# Audio-Beamformer_FPGA_V1_0.net
KiCad netlist of a schematic drawn in Altium Designer
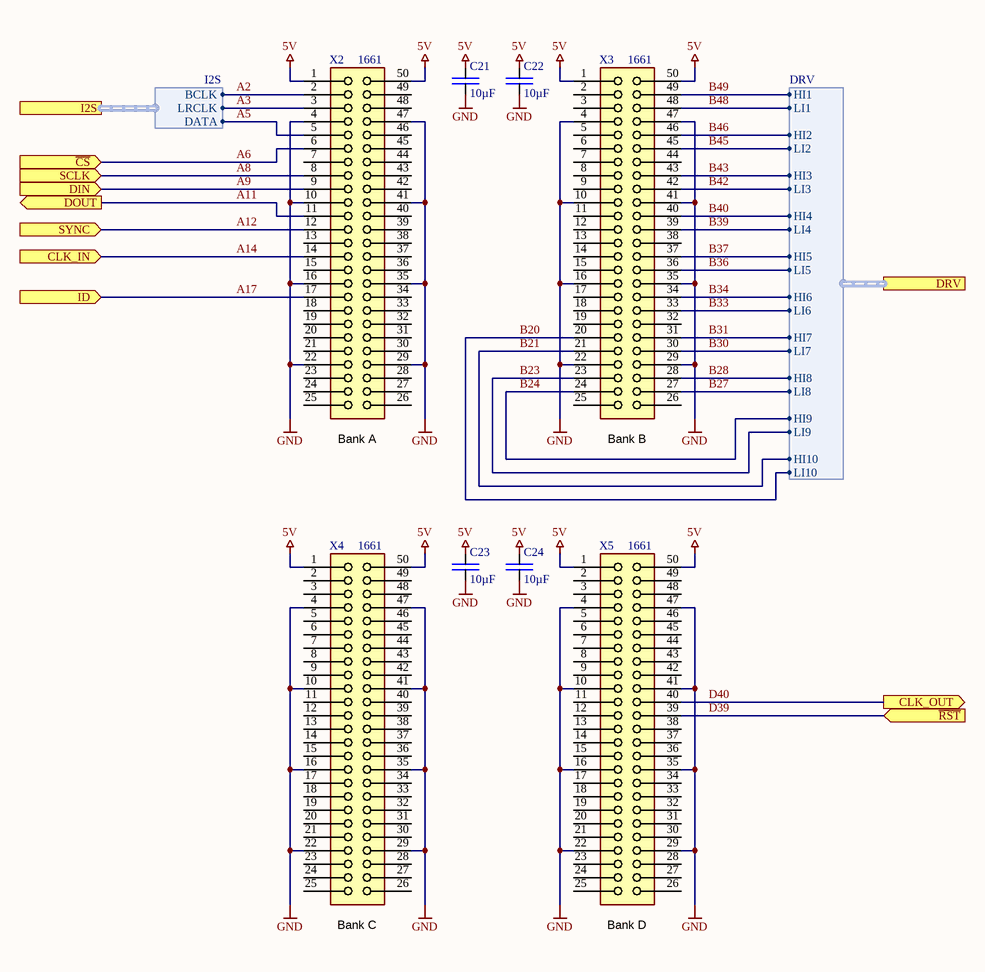
[diagram p0: Audio-Beamformer_FPGA_V1.0.SchDoc]

(export (version "E")
  (design (tool "Eeschema 10.0.6"))
  (components
    (comp (ref "C21")
      (value "10µF")
      (footprint "SMD Keramikkondensator 1206")
      (description "CAP-MK")
      (libsource (lib "AudioAmp") (part "C-CAPACITOR"))
    )
    (comp (ref "C22")
      (value "10µF")
      (footprint "SMD Keramikkondensator 1206")
      (description "CAP-MK")
      (libsource (lib "AudioAmp") (part "C-CAPACITOR"))
    )
    (comp (ref "C23")
      (value "10µF")
      (footprint "SMD Keramikkondensator 1206")
      (description "CAP-MK")
      (libsource (lib "AudioAmp") (part "C-CAPACITOR"))
    )
    (comp (ref "C24")
      (value "10µF")
      (footprint "SMD Keramikkondensator 1206")
      (description "CAP-MK")
      (libsource (lib "AudioAmp") (part "C-CAPACITOR"))
    )
    (comp (ref "X2")
      (value "1661")
      (footprint "SMD Connector (1661)")
      (description "Board-to-Board Connector (Receptacle)")
      (libsource (lib "Quad-Stage-Prototype") (part "X-4UCON_1661"))
    )
    (comp (ref "X3")
      (value "1661")
      (footprint "SMD Connector (1661)")
      (description "Board-to-Board Connector (Receptacle)")
      (libsource (lib "Quad-Stage-Prototype") (part "X-4UCON_1661"))
    )
    (comp (ref "X4")
      (value "1661")
      (footprint "SMD Connector (1661)")
      (description "Board-to-Board Connector (Receptacle)")
      (libsource (lib "Quad-Stage-Prototype") (part "X-4UCON_1661"))
    )
    (comp (ref "X5")
      (value "1661")
      (footprint "SMD Connector (1661)")
      (description "Board-to-Board Connector (Receptacle)")
      (libsource (lib "Quad-Stage-Prototype") (part "X-4UCON_1661"))
    )
  )
  (nets
    (net (code "3") (name "/A2") (class "Default")
      (node (ref "X2") (pin "2") (pinfunction "2_2") (pintype "passive"))
    )
    (net (code "4") (name "/A3") (class "Default")
      (node (ref "X2") (pin "3") (pinfunction "3_3") (pintype "passive"))
    )
    (net (code "5") (name "/A5") (class "Default")
      (node (ref "X2") (pin "5") (pinfunction "5_5") (pintype "passive"))
    )
    (net (code "6") (name "/A6") (class "Default")
      (node (ref "X2") (pin "6") (pinfunction "6_6") (pintype "passive"))
    )
    (net (code "7") (name "/A8") (class "Default")
      (node (ref "X2") (pin "8") (pinfunction "8_8") (pintype "passive"))
    )
    (net (code "8") (name "/A9") (class "Default")
      (node (ref "X2") (pin "9") (pinfunction "9_9") (pintype "passive"))
    )
    (net (code "9") (name "/A11") (class "Default")
      (node (ref "X2") (pin "11") (pinfunction "11_11") (pintype "passive"))
    )
    (net (code "10") (name "/A12") (class "Default")
      (node (ref "X2") (pin "12") (pinfunction "12_12") (pintype "passive"))
    )
    (net (code "11") (name "/A14") (class "Default")
      (node (ref "X2") (pin "14") (pinfunction "14_14") (pintype "passive"))
    )
    (net (code "12") (name "/A17") (class "Default")
      (node (ref "X2") (pin "17") (pinfunction "17_17") (pintype "passive"))
    )
    (net (code "13") (name "/B20") (class "Default")
      (node (ref "X3") (pin "20") (pinfunction "20_20") (pintype "passive"))
    )
    (net (code "14") (name "/B21") (class "Default")
      (node (ref "X3") (pin "21") (pinfunction "21_21") (pintype "passive"))
    )
    (net (code "15") (name "/B23") (class "Default")
      (node (ref "X3") (pin "23") (pinfunction "23_23") (pintype "passive"))
    )
    (net (code "16") (name "/B24") (class "Default")
      (node (ref "X3") (pin "24") (pinfunction "24_24") (pintype "passive"))
    )
    (net (code "17") (name "/B27") (class "Default")
      (node (ref "X3") (pin "27") (pinfunction "27_27") (pintype "passive"))
    )
    (net (code "18") (name "/B28") (class "Default")
      (node (ref "X3") (pin "28") (pinfunction "28_28") (pintype "passive"))
    )
    (net (code "19") (name "/B30") (class "Default")
      (node (ref "X3") (pin "30") (pinfunction "30_30") (pintype "passive"))
    )
    (net (code "20") (name "/B31") (class "Default")
      (node (ref "X3") (pin "31") (pinfunction "31_31") (pintype "passive"))
    )
    (net (code "21") (name "/B33") (class "Default")
      (node (ref "X3") (pin "33") (pinfunction "33_33") (pintype "passive"))
    )
    (net (code "22") (name "/B34") (class "Default")
      (node (ref "X3") (pin "34") (pinfunction "34_34") (pintype "passive"))
    )
    (net (code "23") (name "/B36") (class "Default")
      (node (ref "X3") (pin "36") (pinfunction "36_36") (pintype "passive"))
    )
    (net (code "24") (name "/B37") (class "Default")
      (node (ref "X3") (pin "37") (pinfunction "37_37") (pintype "passive"))
    )
    (net (code "25") (name "/B39") (class "Default")
      (node (ref "X3") (pin "39") (pinfunction "39_39") (pintype "passive"))
    )
    (net (code "26") (name "/B40") (class "Default")
      (node (ref "X3") (pin "40") (pinfunction "40_40") (pintype "passive"))
    )
    (net (code "27") (name "/B42") (class "Default")
      (node (ref "X3") (pin "42") (pinfunction "42_42") (pintype "passive"))
    )
    (net (code "28") (name "/B43") (class "Default")
      (node (ref "X3") (pin "43") (pinfunction "43_43") (pintype "passive"))
    )
    (net (code "29") (name "/B45") (class "Default")
      (node (ref "X3") (pin "45") (pinfunction "45_45") (pintype "passive"))
    )
    (net (code "30") (name "/B46") (class "Default")
      (node (ref "X3") (pin "46") (pinfunction "46_46") (pintype "passive"))
    )
    (net (code "31") (name "/B48") (class "Default")
      (node (ref "X3") (pin "48") (pinfunction "48_48") (pintype "passive"))
    )
    (net (code "32") (name "/B49") (class "Default")
      (node (ref "X3") (pin "49") (pinfunction "49_49") (pintype "passive"))
    )
    (net (code "33") (name "/D39") (class "Default")
      (node (ref "X5") (pin "39") (pinfunction "39_39") (pintype "passive"))
    )
    (net (code "34") (name "/D40") (class "Default")
      (node (ref "X5") (pin "40") (pinfunction "40_40") (pintype "passive"))
    )
    (net (code "37") (name "5V") (class "Default")
      (node (ref "C21") (pin "2") (pinfunction "2_2") (pintype "passive"))
      (node (ref "C22") (pin "2") (pinfunction "2_2") (pintype "passive"))
      (node (ref "C23") (pin "2") (pinfunction "2_2") (pintype "passive"))
      (node (ref "C24") (pin "2") (pinfunction "2_2") (pintype "passive"))
      (node (ref "X2") (pin "1") (pinfunction "1_1") (pintype "passive"))
      (node (ref "X2") (pin "50") (pinfunction "50_50") (pintype "passive"))
      (node (ref "X3") (pin "1") (pinfunction "1_1") (pintype "passive"))
      (node (ref "X3") (pin "50") (pinfunction "50_50") (pintype "passive"))
      (node (ref "X4") (pin "1") (pinfunction "1_1") (pintype "passive"))
      (node (ref "X4") (pin "50") (pinfunction "50_50") (pintype "passive"))
      (node (ref "X5") (pin "1") (pinfunction "1_1") (pintype "passive"))
      (node (ref "X5") (pin "50") (pinfunction "50_50") (pintype "passive"))
    )
    (net (code "38") (name "GND") (class "Default")
      (node (ref "C21") (pin "1") (pinfunction "1_1") (pintype "passive"))
      (node (ref "C22") (pin "1") (pinfunction "1_1") (pintype "passive"))
      (node (ref "C23") (pin "1") (pinfunction "1_1") (pintype "passive"))
      (node (ref "C24") (pin "1") (pinfunction "1_1") (pintype "passive"))
      (node (ref "X2") (pin "10") (pinfunction "10_10") (pintype "passive"))
      (node (ref "X2") (pin "16") (pinfunction "16_16") (pintype "passive"))
      (node (ref "X2") (pin "22") (pinfunction "22_22") (pintype "passive"))
      (node (ref "X2") (pin "29") (pinfunction "29_29") (pintype "passive"))
      (node (ref "X2") (pin "35") (pinfunction "35_35") (pintype "passive"))
      (node (ref "X2") (pin "4") (pinfunction "4_4") (pintype "passive"))
      (node (ref "X2") (pin "41") (pinfunction "41_41") (pintype "passive"))
      (node (ref "X2") (pin "47") (pinfunction "47_47") (pintype "passive"))
      (node (ref "X3") (pin "10") (pinfunction "10_10") (pintype "passive"))
      (node (ref "X3") (pin "16") (pinfunction "16_16") (pintype "passive"))
      (node (ref "X3") (pin "22") (pinfunction "22_22") (pintype "passive"))
      (node (ref "X3") (pin "29") (pinfunction "29_29") (pintype "passive"))
      (node (ref "X3") (pin "35") (pinfunction "35_35") (pintype "passive"))
      (node (ref "X3") (pin "4") (pinfunction "4_4") (pintype "passive"))
      (node (ref "X3") (pin "41") (pinfunction "41_41") (pintype "passive"))
      (node (ref "X3") (pin "47") (pinfunction "47_47") (pintype "passive"))
      (node (ref "X4") (pin "10") (pinfunction "10_10") (pintype "passive"))
      (node (ref "X4") (pin "16") (pinfunction "16_16") (pintype "passive"))
      (node (ref "X4") (pin "22") (pinfunction "22_22") (pintype "passive"))
      (node (ref "X4") (pin "29") (pinfunction "29_29") (pintype "passive"))
      (node (ref "X4") (pin "35") (pinfunction "35_35") (pintype "passive"))
      (node (ref "X4") (pin "4") (pinfunction "4_4") (pintype "passive"))
      (node (ref "X4") (pin "41") (pinfunction "41_41") (pintype "passive"))
      (node (ref "X4") (pin "47") (pinfunction "47_47") (pintype "passive"))
      (node (ref "X5") (pin "10") (pinfunction "10_10") (pintype "passive"))
      (node (ref "X5") (pin "16") (pinfunction "16_16") (pintype "passive"))
      (node (ref "X5") (pin "22") (pinfunction "22_22") (pintype "passive"))
      (node (ref "X5") (pin "29") (pinfunction "29_29") (pintype "passive"))
      (node (ref "X5") (pin "35") (pinfunction "35_35") (pintype "passive"))
      (node (ref "X5") (pin "4") (pinfunction "4_4") (pintype "passive"))
      (node (ref "X5") (pin "41") (pinfunction "41_41") (pintype "passive"))
      (node (ref "X5") (pin "47") (pinfunction "47_47") (pintype "passive"))
    )
    (net (code "39") (name "unconnected-(X2-Pad7)") (class "Default")
      (node (ref "X2") (pin "7") (pinfunction "7_7") (pintype "passive"))
    )
    (net (code "40") (name "unconnected-(X2-Pad13)") (class "Default")
      (node (ref "X2") (pin "13") (pinfunction "13_13") (pintype "passive"))
    )
    (net (code "41") (name "unconnected-(X2-Pad15)") (class "Default")
      (node (ref "X2") (pin "15") (pinfunction "15_15") (pintype "passive"))
    )
    (net (code "42") (name "unconnected-(X2-Pad18)") (class "Default")
      (node (ref "X2") (pin "18") (pinfunction "18_18") (pintype "passive"))
    )
    (net (code "43") (name "unconnected-(X2-Pad19)") (class "Default")
      (node (ref "X2") (pin "19") (pinfunction "19_19") (pintype "passive"))
    )
    (net (code "44") (name "unconnected-(X2-Pad20)") (class "Default")
      (node (ref "X2") (pin "20") (pinfunction "20_20") (pintype "passive"))
    )
    (net (code "45") (name "unconnected-(X2-Pad21)") (class "Default")
      (node (ref "X2") (pin "21") (pinfunction "21_21") (pintype "passive"))
    )
    (net (code "46") (name "unconnected-(X2-Pad23)") (class "Default")
      (node (ref "X2") (pin "23") (pinfunction "23_23") (pintype "passive"))
    )
    (net (code "47") (name "unconnected-(X2-Pad24)") (class "Default")
      (node (ref "X2") (pin "24") (pinfunction "24_24") (pintype "passive"))
    )
    (net (code "48") (name "unconnected-(X2-Pad25)") (class "Default")
      (node (ref "X2") (pin "25") (pinfunction "25_25") (pintype "passive"))
    )
    (net (code "49") (name "unconnected-(X2-Pad26)") (class "Default")
      (node (ref "X2") (pin "26") (pinfunction "26_26") (pintype "passive"))
    )
    (net (code "50") (name "unconnected-(X2-Pad27)") (class "Default")
      (node (ref "X2") (pin "27") (pinfunction "27_27") (pintype "passive"))
    )
    (net (code "51") (name "unconnected-(X2-Pad28)") (class "Default")
      (node (ref "X2") (pin "28") (pinfunction "28_28") (pintype "passive"))
    )
    (net (code "52") (name "unconnected-(X2-Pad30)") (class "Default")
      (node (ref "X2") (pin "30") (pinfunction "30_30") (pintype "passive"))
    )
    (net (code "53") (name "unconnected-(X2-Pad31)") (class "Default")
      (node (ref "X2") (pin "31") (pinfunction "31_31") (pintype "passive"))
    )
    (net (code "54") (name "unconnected-(X2-Pad32)") (class "Default")
      (node (ref "X2") (pin "32") (pinfunction "32_32") (pintype "passive"))
    )
    (net (code "55") (name "unconnected-(X2-Pad33)") (class "Default")
      (node (ref "X2") (pin "33") (pinfunction "33_33") (pintype "passive"))
    )
    (net (code "56") (name "unconnected-(X2-Pad34)") (class "Default")
      (node (ref "X2") (pin "34") (pinfunction "34_34") (pintype "passive"))
    )
    (net (code "57") (name "unconnected-(X2-Pad36)") (class "Default")
      (node (ref "X2") (pin "36") (pinfunction "36_36") (pintype "passive"))
    )
    (net (code "58") (name "unconnected-(X2-Pad37)") (class "Default")
      (node (ref "X2") (pin "37") (pinfunction "37_37") (pintype "passive"))
    )
    (net (code "59") (name "unconnected-(X2-Pad38)") (class "Default")
      (node (ref "X2") (pin "38") (pinfunction "38_38") (pintype "passive"))
    )
    (net (code "60") (name "unconnected-(X2-Pad39)") (class "Default")
      (node (ref "X2") (pin "39") (pinfunction "39_39") (pintype "passive"))
    )
    (net (code "61") (name "unconnected-(X2-Pad40)") (class "Default")
      (node (ref "X2") (pin "40") (pinfunction "40_40") (pintype "passive"))
    )
    (net (code "62") (name "unconnected-(X2-Pad42)") (class "Default")
      (node (ref "X2") (pin "42") (pinfunction "42_42") (pintype "passive"))
    )
    (net (code "63") (name "unconnected-(X2-Pad43)") (class "Default")
      (node (ref "X2") (pin "43") (pinfunction "43_43") (pintype "passive"))
    )
    (net (code "64") (name "unconnected-(X2-Pad44)") (class "Default")
      (node (ref "X2") (pin "44") (pinfunction "44_44") (pintype "passive"))
    )
    (net (code "65") (name "unconnected-(X2-Pad45)") (class "Default")
      (node (ref "X2") (pin "45") (pinfunction "45_45") (pintype "passive"))
    )
    (net (code "66") (name "unconnected-(X2-Pad46)") (class "Default")
      (node (ref "X2") (pin "46") (pinfunction "46_46") (pintype "passive"))
    )
    (net (code "67") (name "unconnected-(X2-Pad48)") (class "Default")
      (node (ref "X2") (pin "48") (pinfunction "48_48") (pintype "passive"))
    )
    (net (code "68") (name "unconnected-(X2-Pad49)") (class "Default")
      (node (ref "X2") (pin "49") (pinfunction "49_49") (pintype "passive"))
    )
    (net (code "69") (name "unconnected-(X3-Pad2)") (class "Default")
      (node (ref "X3") (pin "2") (pinfunction "2_2") (pintype "passive"))
    )
    (net (code "70") (name "unconnected-(X3-Pad3)") (class "Default")
      (node (ref "X3") (pin "3") (pinfunction "3_3") (pintype "passive"))
    )
    (net (code "71") (name "unconnected-(X3-Pad5)") (class "Default")
      (node (ref "X3") (pin "5") (pinfunction "5_5") (pintype "passive"))
    )
    (net (code "72") (name "unconnected-(X3-Pad6)") (class "Default")
      (node (ref "X3") (pin "6") (pinfunction "6_6") (pintype "passive"))
    )
    (net (code "73") (name "unconnected-(X3-Pad7)") (class "Default")
      (node (ref "X3") (pin "7") (pinfunction "7_7") (pintype "passive"))
    )
    (net (code "74") (name "unconnected-(X3-Pad8)") (class "Default")
      (node (ref "X3") (pin "8") (pinfunction "8_8") (pintype "passive"))
    )
    (net (code "75") (name "unconnected-(X3-Pad9)") (class "Default")
      (node (ref "X3") (pin "9") (pinfunction "9_9") (pintype "passive"))
    )
    (net (code "76") (name "unconnected-(X3-Pad11)") (class "Default")
      (node (ref "X3") (pin "11") (pinfunction "11_11") (pintype "passive"))
    )
    (net (code "77") (name "unconnected-(X3-Pad12)") (class "Default")
      (node (ref "X3") (pin "12") (pinfunction "12_12") (pintype "passive"))
    )
    (net (code "78") (name "unconnected-(X3-Pad13)") (class "Default")
      (node (ref "X3") (pin "13") (pinfunction "13_13") (pintype "passive"))
    )
    (net (code "79") (name "unconnected-(X3-Pad14)") (class "Default")
      (node (ref "X3") (pin "14") (pinfunction "14_14") (pintype "passive"))
    )
    (net (code "80") (name "unconnected-(X3-Pad15)") (class "Default")
      (node (ref "X3") (pin "15") (pinfunction "15_15") (pintype "passive"))
    )
    (net (code "81") (name "unconnected-(X3-Pad17)") (class "Default")
      (node (ref "X3") (pin "17") (pinfunction "17_17") (pintype "passive"))
    )
    (net (code "82") (name "unconnected-(X3-Pad18)") (class "Default")
      (node (ref "X3") (pin "18") (pinfunction "18_18") (pintype "passive"))
    )
    (net (code "83") (name "unconnected-(X3-Pad19)") (class "Default")
      (node (ref "X3") (pin "19") (pinfunction "19_19") (pintype "passive"))
    )
    (net (code "84") (name "unconnected-(X3-Pad25)") (class "Default")
      (node (ref "X3") (pin "25") (pinfunction "25_25") (pintype "passive"))
    )
    (net (code "85") (name "unconnected-(X3-Pad26)") (class "Default")
      (node (ref "X3") (pin "26") (pinfunction "26_26") (pintype "passive"))
    )
    (net (code "86") (name "unconnected-(X3-Pad32)") (class "Default")
      (node (ref "X3") (pin "32") (pinfunction "32_32") (pintype "passive"))
    )
    (net (code "87") (name "unconnected-(X3-Pad38)") (class "Default")
      (node (ref "X3") (pin "38") (pinfunction "38_38") (pintype "passive"))
    )
    (net (code "88") (name "unconnected-(X3-Pad44)") (class "Default")
      (node (ref "X3") (pin "44") (pinfunction "44_44") (pintype "passive"))
    )
    (net (code "89") (name "unconnected-(X4-Pad2)") (class "Default")
      (node (ref "X4") (pin "2") (pinfunction "2_2") (pintype "passive"))
    )
    (net (code "90") (name "unconnected-(X4-Pad3)") (class "Default")
      (node (ref "X4") (pin "3") (pinfunction "3_3") (pintype "passive"))
    )
    (net (code "91") (name "unconnected-(X4-Pad5)") (class "Default")
      (node (ref "X4") (pin "5") (pinfunction "5_5") (pintype "passive"))
    )
    (net (code "92") (name "unconnected-(X4-Pad6)") (class "Default")
      (node (ref "X4") (pin "6") (pinfunction "6_6") (pintype "passive"))
    )
    (net (code "93") (name "unconnected-(X4-Pad7)") (class "Default")
      (node (ref "X4") (pin "7") (pinfunction "7_7") (pintype "passive"))
    )
    (net (code "94") (name "unconnected-(X4-Pad8)") (class "Default")
      (node (ref "X4") (pin "8") (pinfunction "8_8") (pintype "passive"))
    )
    (net (code "95") (name "unconnected-(X4-Pad9)") (class "Default")
      (node (ref "X4") (pin "9") (pinfunction "9_9") (pintype "passive"))
    )
    (net (code "96") (name "unconnected-(X4-Pad11)") (class "Default")
      (node (ref "X4") (pin "11") (pinfunction "11_11") (pintype "passive"))
    )
    (net (code "97") (name "unconnected-(X4-Pad12)") (class "Default")
      (node (ref "X4") (pin "12") (pinfunction "12_12") (pintype "passive"))
    )
    (net (code "98") (name "unconnected-(X4-Pad13)") (class "Default")
      (node (ref "X4") (pin "13") (pinfunction "13_13") (pintype "passive"))
    )
    (net (code "99") (name "unconnected-(X4-Pad14)") (class "Default")
      (node (ref "X4") (pin "14") (pinfunction "14_14") (pintype "passive"))
    )
    (net (code "100") (name "unconnected-(X4-Pad15)") (class "Default")
      (node (ref "X4") (pin "15") (pinfunction "15_15") (pintype "passive"))
    )
    (net (code "101") (name "unconnected-(X4-Pad17)") (class "Default")
      (node (ref "X4") (pin "17") (pinfunction "17_17") (pintype "passive"))
    )
    (net (code "102") (name "unconnected-(X4-Pad18)") (class "Default")
      (node (ref "X4") (pin "18") (pinfunction "18_18") (pintype "passive"))
    )
    (net (code "103") (name "unconnected-(X4-Pad19)") (class "Default")
      (node (ref "X4") (pin "19") (pinfunction "19_19") (pintype "passive"))
    )
    (net (code "104") (name "unconnected-(X4-Pad20)") (class "Default")
      (node (ref "X4") (pin "20") (pinfunction "20_20") (pintype "passive"))
    )
    (net (code "105") (name "unconnected-(X4-Pad21)") (class "Default")
      (node (ref "X4") (pin "21") (pinfunction "21_21") (pintype "passive"))
    )
    (net (code "106") (name "unconnected-(X4-Pad23)") (class "Default")
      (node (ref "X4") (pin "23") (pinfunction "23_23") (pintype "passive"))
    )
    (net (code "107") (name "unconnected-(X4-Pad24)") (class "Default")
      (node (ref "X4") (pin "24") (pinfunction "24_24") (pintype "passive"))
    )
    (net (code "108") (name "unconnected-(X4-Pad25)") (class "Default")
      (node (ref "X4") (pin "25") (pinfunction "25_25") (pintype "passive"))
    )
    (net (code "109") (name "unconnected-(X4-Pad26)") (class "Default")
      (node (ref "X4") (pin "26") (pinfunction "26_26") (pintype "passive"))
    )
    (net (code "110") (name "unconnected-(X4-Pad27)") (class "Default")
      (node (ref "X4") (pin "27") (pinfunction "27_27") (pintype "passive"))
    )
    (net (code "111") (name "unconnected-(X4-Pad28)") (class "Default")
      (node (ref "X4") (pin "28") (pinfunction "28_28") (pintype "passive"))
    )
    (net (code "112") (name "unconnected-(X4-Pad30)") (class "Default")
      (node (ref "X4") (pin "30") (pinfunction "30_30") (pintype "passive"))
    )
    (net (code "113") (name "unconnected-(X4-Pad31)") (class "Default")
      (node (ref "X4") (pin "31") (pinfunction "31_31") (pintype "passive"))
    )
    (net (code "114") (name "unconnected-(X4-Pad32)") (class "Default")
      (node (ref "X4") (pin "32") (pinfunction "32_32") (pintype "passive"))
    )
    (net (code "115") (name "unconnected-(X4-Pad33)") (class "Default")
      (node (ref "X4") (pin "33") (pinfunction "33_33") (pintype "passive"))
    )
    (net (code "116") (name "unconnected-(X4-Pad34)") (class "Default")
      (node (ref "X4") (pin "34") (pinfunction "34_34") (pintype "passive"))
    )
    (net (code "117") (name "unconnected-(X4-Pad36)") (class "Default")
      (node (ref "X4") (pin "36") (pinfunction "36_36") (pintype "passive"))
    )
    (net (code "118") (name "unconnected-(X4-Pad37)") (class "Default")
      (node (ref "X4") (pin "37") (pinfunction "37_37") (pintype "passive"))
    )
    (net (code "119") (name "unconnected-(X4-Pad38)") (class "Default")
      (node (ref "X4") (pin "38") (pinfunction "38_38") (pintype "passive"))
    )
    (net (code "120") (name "unconnected-(X4-Pad39)") (class "Default")
      (node (ref "X4") (pin "39") (pinfunction "39_39") (pintype "passive"))
    )
    (net (code "121") (name "unconnected-(X4-Pad40)") (class "Default")
      (node (ref "X4") (pin "40") (pinfunction "40_40") (pintype "passive"))
    )
    (net (code "122") (name "unconnected-(X4-Pad42)") (class "Default")
      (node (ref "X4") (pin "42") (pinfunction "42_42") (pintype "passive"))
    )
    (net (code "123") (name "unconnected-(X4-Pad43)") (class "Default")
      (node (ref "X4") (pin "43") (pinfunction "43_43") (pintype "passive"))
    )
    (net (code "124") (name "unconnected-(X4-Pad44)") (class "Default")
      (node (ref "X4") (pin "44") (pinfunction "44_44") (pintype "passive"))
    )
    (net (code "125") (name "unconnected-(X4-Pad45)") (class "Default")
      (node (ref "X4") (pin "45") (pinfunction "45_45") (pintype "passive"))
    )
    (net (code "126") (name "unconnected-(X4-Pad46)") (class "Default")
      (node (ref "X4") (pin "46") (pinfunction "46_46") (pintype "passive"))
    )
    (net (code "127") (name "unconnected-(X4-Pad48)") (class "Default")
      (node (ref "X4") (pin "48") (pinfunction "48_48") (pintype "passive"))
    )
    (net (code "128") (name "unconnected-(X4-Pad49)") (class "Default")
      (node (ref "X4") (pin "49") (pinfunction "49_49") (pintype "passive"))
    )
    (net (code "129") (name "unconnected-(X5-Pad2)") (class "Default")
      (node (ref "X5") (pin "2") (pinfunction "2_2") (pintype "passive"))
    )
    (net (code "130") (name "unconnected-(X5-Pad3)") (class "Default")
      (node (ref "X5") (pin "3") (pinfunction "3_3") (pintype "passive"))
    )
    (net (code "131") (name "unconnected-(X5-Pad5)") (class "Default")
      (node (ref "X5") (pin "5") (pinfunction "5_5") (pintype "passive"))
    )
    (net (code "132") (name "unconnected-(X5-Pad6)") (class "Default")
      (node (ref "X5") (pin "6") (pinfunction "6_6") (pintype "passive"))
    )
    (net (code "133") (name "unconnected-(X5-Pad7)") (class "Default")
      (node (ref "X5") (pin "7") (pinfunction "7_7") (pintype "passive"))
    )
    (net (code "134") (name "unconnected-(X5-Pad8)") (class "Default")
      (node (ref "X5") (pin "8") (pinfunction "8_8") (pintype "passive"))
    )
    (net (code "135") (name "unconnected-(X5-Pad9)") (class "Default")
      (node (ref "X5") (pin "9") (pinfunction "9_9") (pintype "passive"))
    )
    (net (code "136") (name "unconnected-(X5-Pad11)") (class "Default")
      (node (ref "X5") (pin "11") (pinfunction "11_11") (pintype "passive"))
    )
    (net (code "137") (name "unconnected-(X5-Pad12)") (class "Default")
      (node (ref "X5") (pin "12") (pinfunction "12_12") (pintype "passive"))
    )
    (net (code "138") (name "unconnected-(X5-Pad13)") (class "Default")
      (node (ref "X5") (pin "13") (pinfunction "13_13") (pintype "passive"))
    )
    (net (code "139") (name "unconnected-(X5-Pad14)") (class "Default")
      (node (ref "X5") (pin "14") (pinfunction "14_14") (pintype "passive"))
    )
    (net (code "140") (name "unconnected-(X5-Pad15)") (class "Default")
      (node (ref "X5") (pin "15") (pinfunction "15_15") (pintype "passive"))
    )
    (net (code "141") (name "unconnected-(X5-Pad17)") (class "Default")
      (node (ref "X5") (pin "17") (pinfunction "17_17") (pintype "passive"))
    )
    (net (code "142") (name "unconnected-(X5-Pad18)") (class "Default")
      (node (ref "X5") (pin "18") (pinfunction "18_18") (pintype "passive"))
    )
    (net (code "143") (name "unconnected-(X5-Pad19)") (class "Default")
      (node (ref "X5") (pin "19") (pinfunction "19_19") (pintype "passive"))
    )
    (net (code "144") (name "unconnected-(X5-Pad20)") (class "Default")
      (node (ref "X5") (pin "20") (pinfunction "20_20") (pintype "passive"))
    )
    (net (code "145") (name "unconnected-(X5-Pad21)") (class "Default")
      (node (ref "X5") (pin "21") (pinfunction "21_21") (pintype "passive"))
    )
    (net (code "146") (name "unconnected-(X5-Pad23)") (class "Default")
      (node (ref "X5") (pin "23") (pinfunction "23_23") (pintype "passive"))
    )
    (net (code "147") (name "unconnected-(X5-Pad24)") (class "Default")
      (node (ref "X5") (pin "24") (pinfunction "24_24") (pintype "passive"))
    )
    (net (code "148") (name "unconnected-(X5-Pad25)") (class "Default")
      (node (ref "X5") (pin "25") (pinfunction "25_25") (pintype "passive"))
    )
    (net (code "149") (name "unconnected-(X5-Pad26)") (class "Default")
      (node (ref "X5") (pin "26") (pinfunction "26_26") (pintype "passive"))
    )
    (net (code "150") (name "unconnected-(X5-Pad27)") (class "Default")
      (node (ref "X5") (pin "27") (pinfunction "27_27") (pintype "passive"))
    )
    (net (code "151") (name "unconnected-(X5-Pad28)") (class "Default")
      (node (ref "X5") (pin "28") (pinfunction "28_28") (pintype "passive"))
    )
    (net (code "152") (name "unconnected-(X5-Pad30)") (class "Default")
      (node (ref "X5") (pin "30") (pinfunction "30_30") (pintype "passive"))
    )
    (net (code "153") (name "unconnected-(X5-Pad31)") (class "Default")
      (node (ref "X5") (pin "31") (pinfunction "31_31") (pintype "passive"))
    )
    (net (code "154") (name "unconnected-(X5-Pad32)") (class "Default")
      (node (ref "X5") (pin "32") (pinfunction "32_32") (pintype "passive"))
    )
    (net (code "155") (name "unconnected-(X5-Pad33)") (class "Default")
      (node (ref "X5") (pin "33") (pinfunction "33_33") (pintype "passive"))
    )
    (net (code "156") (name "unconnected-(X5-Pad34)") (class "Default")
      (node (ref "X5") (pin "34") (pinfunction "34_34") (pintype "passive"))
    )
    (net (code "157") (name "unconnected-(X5-Pad36)") (class "Default")
      (node (ref "X5") (pin "36") (pinfunction "36_36") (pintype "passive"))
    )
    (net (code "158") (name "unconnected-(X5-Pad37)") (class "Default")
      (node (ref "X5") (pin "37") (pinfunction "37_37") (pintype "passive"))
    )
    (net (code "159") (name "unconnected-(X5-Pad38)") (class "Default")
      (node (ref "X5") (pin "38") (pinfunction "38_38") (pintype "passive"))
    )
    (net (code "160") (name "unconnected-(X5-Pad42)") (class "Default")
      (node (ref "X5") (pin "42") (pinfunction "42_42") (pintype "passive"))
    )
    (net (code "161") (name "unconnected-(X5-Pad43)") (class "Default")
      (node (ref "X5") (pin "43") (pinfunction "43_43") (pintype "passive"))
    )
    (net (code "162") (name "unconnected-(X5-Pad44)") (class "Default")
      (node (ref "X5") (pin "44") (pinfunction "44_44") (pintype "passive"))
    )
    (net (code "163") (name "unconnected-(X5-Pad45)") (class "Default")
      (node (ref "X5") (pin "45") (pinfunction "45_45") (pintype "passive"))
    )
    (net (code "164") (name "unconnected-(X5-Pad46)") (class "Default")
      (node (ref "X5") (pin "46") (pinfunction "46_46") (pintype "passive"))
    )
    (net (code "165") (name "unconnected-(X5-Pad48)") (class "Default")
      (node (ref "X5") (pin "48") (pinfunction "48_48") (pintype "passive"))
    )
    (net (code "166") (name "unconnected-(X5-Pad49)") (class "Default")
      (node (ref "X5") (pin "49") (pinfunction "49_49") (pintype "passive"))
    )
  )
)
